# bristol_longshot.net
KiCad netlist of a schematic drawn in EAGLE
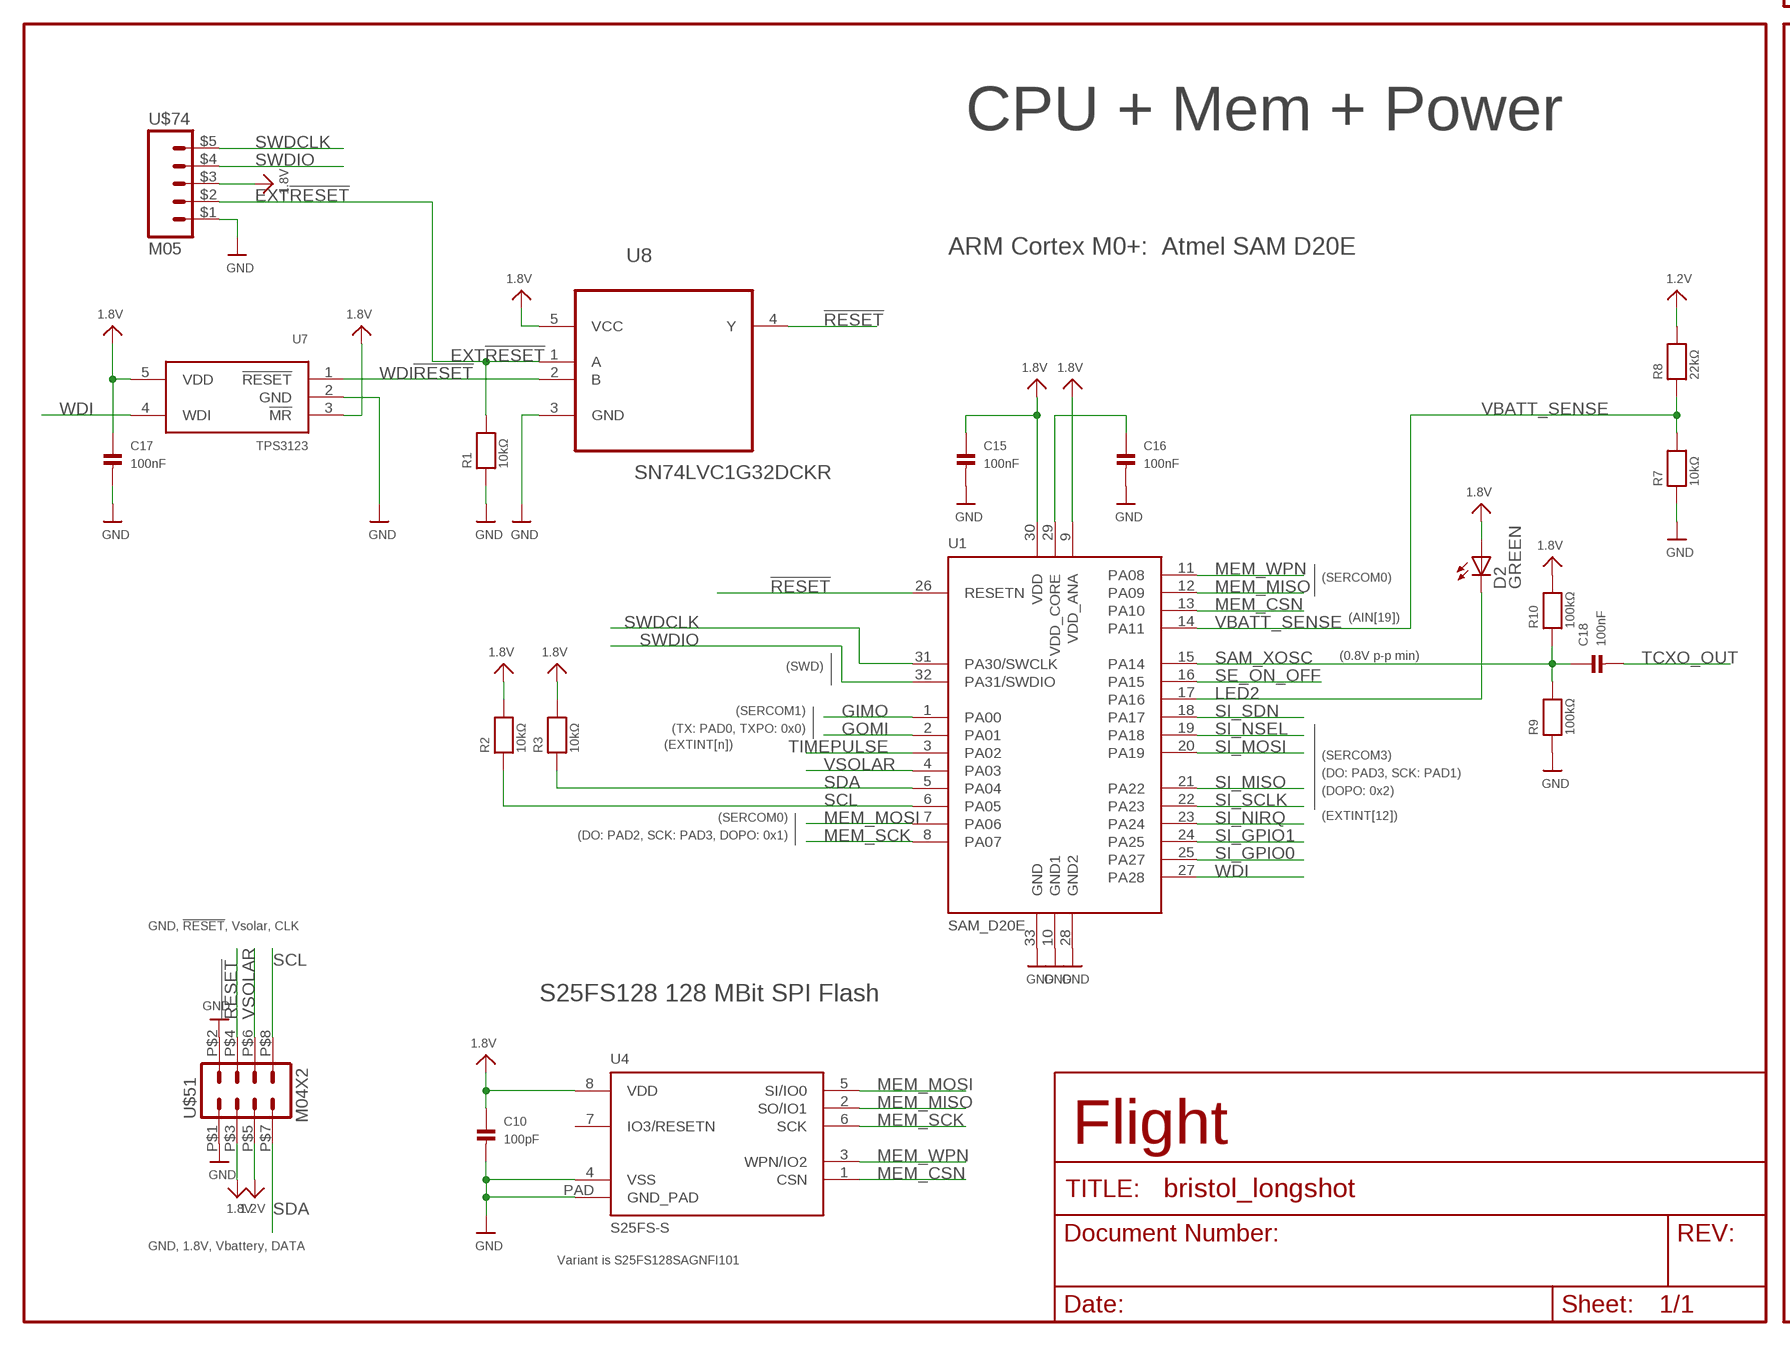
[diagram p0: schematic, sheet 1, part 1 of 2]
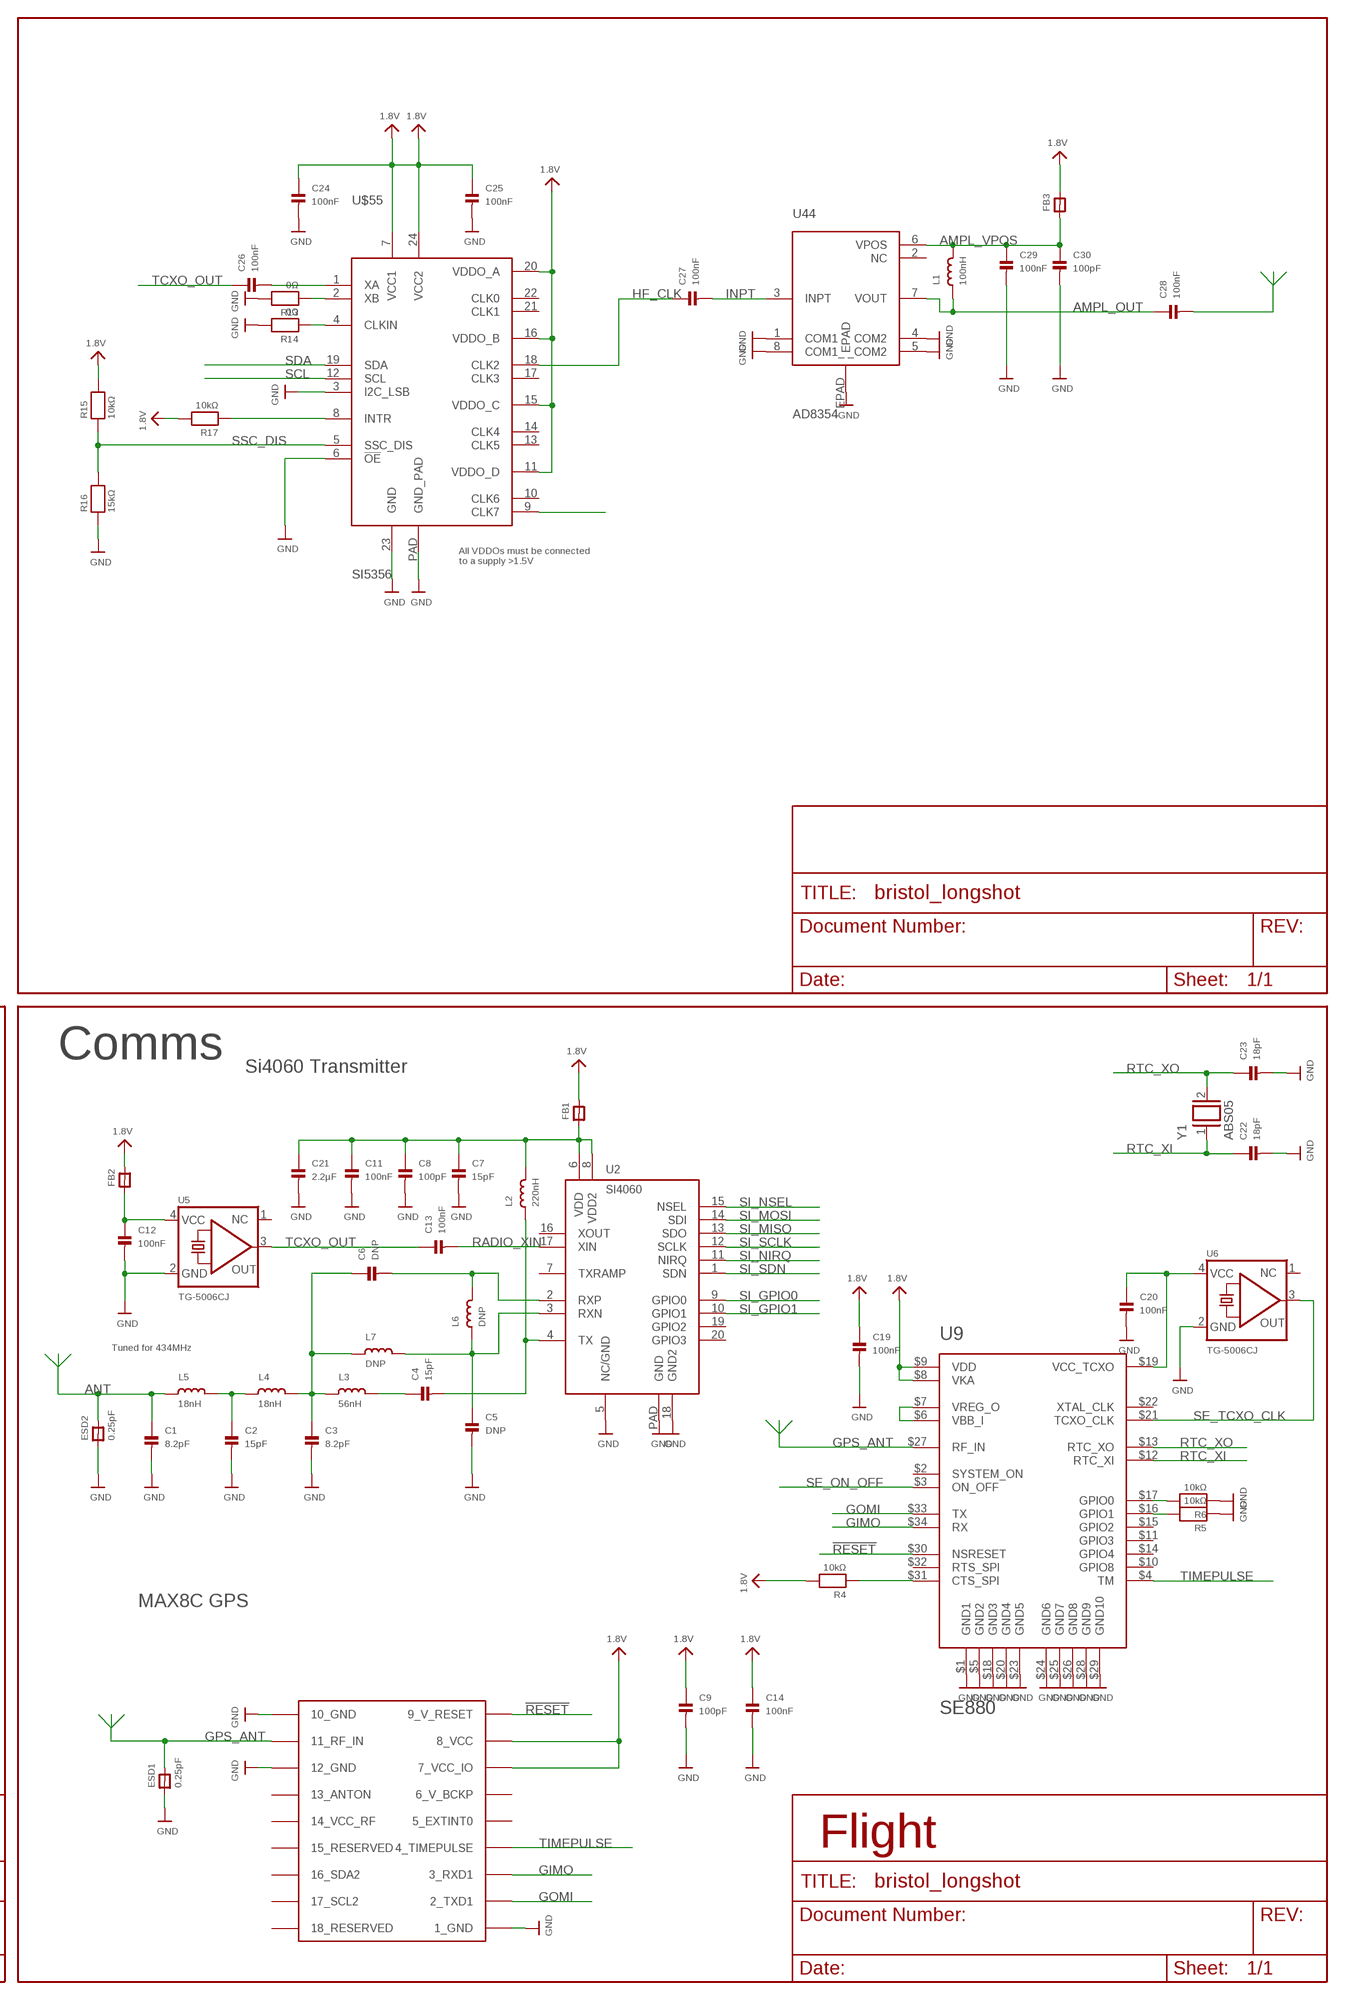
[diagram p1: schematic, sheet 1, part 2 of 2]

(export (version "E")
  (design (tool "Eeschema 10.0.6"))
  (components
    (comp (ref "C1")
      (value "8.2pF")
      (footprint "eagle-import:_0402")
      (libsource (lib "eagle-import") (part "CAP_CERAMIC_0402"))
    )
    (comp (ref "C2")
      (value "15pF")
      (footprint "eagle-import:_0402")
      (libsource (lib "eagle-import") (part "CAP_CERAMIC_0402"))
    )
    (comp (ref "C3")
      (value "8.2pF")
      (footprint "eagle-import:_0402")
      (libsource (lib "eagle-import") (part "CAP_CERAMIC_0402"))
    )
    (comp (ref "C4")
      (value "15pF")
      (footprint "eagle-import:_0402")
      (libsource (lib "eagle-import") (part "CAP_CERAMIC_0402"))
    )
    (comp (ref "C5")
      (value "DNP")
      (footprint "eagle-import:_0402")
      (libsource (lib "eagle-import") (part "CAP_CERAMIC_0402"))
    )
    (comp (ref "C6")
      (value "DNP")
      (footprint "eagle-import:_0402")
      (libsource (lib "eagle-import") (part "CAP_CERAMIC_0402"))
    )
    (comp (ref "C7")
      (value "15pF")
      (footprint "eagle-import:_0402")
      (libsource (lib "eagle-import") (part "CAP_CERAMIC_0402"))
    )
    (comp (ref "C8")
      (value "100pF")
      (footprint "eagle-import:_0402")
      (libsource (lib "eagle-import") (part "CAP_CERAMIC_0402"))
    )
    (comp (ref "C9")
      (value "100pF")
      (footprint "eagle-import:_0402")
      (libsource (lib "eagle-import") (part "CAP_CERAMIC_0402"))
    )
    (comp (ref "C10")
      (value "100pF")
      (footprint "eagle-import:_0402")
      (libsource (lib "eagle-import") (part "CAP_CERAMIC_0402"))
    )
    (comp (ref "C11")
      (value "100nF")
      (footprint "eagle-import:_0402")
      (libsource (lib "eagle-import") (part "CAP_CERAMIC_0402"))
    )
    (comp (ref "C12")
      (value "100nF")
      (footprint "eagle-import:_0402")
      (libsource (lib "eagle-import") (part "CAP_CERAMIC_0402"))
    )
    (comp (ref "C13")
      (value "100nF")
      (footprint "eagle-import:_0402")
      (libsource (lib "eagle-import") (part "CAP_CERAMIC_0402"))
    )
    (comp (ref "C14")
      (value "100nF")
      (footprint "eagle-import:_0402")
      (libsource (lib "eagle-import") (part "CAP_CERAMIC_0402"))
    )
    (comp (ref "C15")
      (value "100nF")
      (footprint "eagle-import:_0402")
      (libsource (lib "eagle-import") (part "CAP_CERAMIC_0402"))
    )
    (comp (ref "C16")
      (value "100nF")
      (footprint "eagle-import:_0402")
      (libsource (lib "eagle-import") (part "CAP_CERAMIC_0402"))
    )
    (comp (ref "C17")
      (value "100nF")
      (footprint "eagle-import:_0402")
      (libsource (lib "eagle-import") (part "CAP_CERAMIC_0402"))
    )
    (comp (ref "C18")
      (value "100nF")
      (footprint "eagle-import:_0402")
      (libsource (lib "eagle-import") (part "CAP_CERAMIC_0402"))
    )
    (comp (ref "C19")
      (value "100nF")
      (footprint "eagle-import:_0402")
      (libsource (lib "eagle-import") (part "CAP_CERAMIC_0402"))
    )
    (comp (ref "C20")
      (value "100nF")
      (footprint "eagle-import:_0402")
      (libsource (lib "eagle-import") (part "CAP_CERAMIC_0402"))
    )
    (comp (ref "C21")
      (value "2.2µF")
      (footprint "eagle-import:_0402")
      (libsource (lib "eagle-import") (part "CAP_CERAMIC_0402"))
    )
    (comp (ref "C22")
      (value "18pF")
      (footprint "eagle-import:_0402")
      (libsource (lib "eagle-import") (part "CAP_CERAMIC_0402"))
    )
    (comp (ref "C23")
      (value "18pF")
      (footprint "eagle-import:_0402")
      (libsource (lib "eagle-import") (part "CAP_CERAMIC_0402"))
    )
    (comp (ref "C24")
      (value "100nF")
      (footprint "eagle-import:_0402")
      (libsource (lib "eagle-import") (part "CAP_CERAMIC_0402"))
    )
    (comp (ref "C25")
      (value "100nF")
      (footprint "eagle-import:_0402")
      (libsource (lib "eagle-import") (part "CAP_CERAMIC_0402"))
    )
    (comp (ref "C26")
      (value "100nF")
      (footprint "eagle-import:_0402")
      (libsource (lib "eagle-import") (part "CAP_CERAMIC_0402"))
    )
    (comp (ref "C27")
      (value "100nF")
      (footprint "eagle-import:_0402")
      (libsource (lib "eagle-import") (part "CAP_CERAMIC_0402"))
    )
    (comp (ref "C28")
      (value "100nF")
      (footprint "eagle-import:_0402")
      (libsource (lib "eagle-import") (part "CAP_CERAMIC_0402"))
    )
    (comp (ref "C29")
      (value "100nF")
      (footprint "eagle-import:_0402")
      (libsource (lib "eagle-import") (part "CAP_CERAMIC_0402"))
    )
    (comp (ref "C30")
      (value "100pF")
      (footprint "eagle-import:_0402")
      (libsource (lib "eagle-import") (part "CAP_CERAMIC_0402"))
    )
    (comp (ref "D2")
      (value "GREEN")
      (footprint "eagle-import:CHIPLED_0603")
      (libsource (lib "eagle-import") (part "LEDCHIPLED_0603"))
    )
    (comp (ref "ESD1")
      (value "0.25pF")
      (footprint "eagle-import:_0603MP")
      (libsource (lib "eagle-import") (part "FERRITE_0603MP"))
    )
    (comp (ref "ESD2")
      (value "0.25pF")
      (footprint "eagle-import:_0603MP")
      (libsource (lib "eagle-import") (part "FERRITE_0603MP"))
    )
    (comp (ref "FB1")
      (value "FERRITE_0402")
      (footprint "eagle-import:_0402")
      (libsource (lib "eagle-import") (part "FERRITE_0402"))
    )
    (comp (ref "FB2")
      (value "FERRITE_0402")
      (footprint "eagle-import:_0402")
      (libsource (lib "eagle-import") (part "FERRITE_0402"))
    )
    (comp (ref "FB3")
      (value "FERRITE_0402")
      (footprint "eagle-import:_0402")
      (libsource (lib "eagle-import") (part "FERRITE_0402"))
    )
    (comp (ref "L1")
      (value "100nH")
      (footprint "eagle-import:_0402")
      (libsource (lib "eagle-import") (part "INDUCTOR_0402"))
    )
    (comp (ref "L2")
      (value "220nH")
      (footprint "eagle-import:_0402")
      (libsource (lib "eagle-import") (part "INDUCTOR_0402"))
    )
    (comp (ref "L3")
      (value "56nH")
      (footprint "eagle-import:_0402")
      (libsource (lib "eagle-import") (part "INDUCTOR_0402"))
    )
    (comp (ref "L4")
      (value "18nH")
      (footprint "eagle-import:_0402")
      (libsource (lib "eagle-import") (part "INDUCTOR_0402"))
    )
    (comp (ref "L5")
      (value "18nH")
      (footprint "eagle-import:_0402")
      (libsource (lib "eagle-import") (part "INDUCTOR_0402"))
    )
    (comp (ref "L6")
      (value "DNP")
      (footprint "eagle-import:_0402")
      (libsource (lib "eagle-import") (part "INDUCTOR_0402"))
    )
    (comp (ref "L7")
      (value "DNP")
      (footprint "eagle-import:_0402")
      (libsource (lib "eagle-import") (part "INDUCTOR_0402"))
    )
    (comp (ref "R1")
      (value "10kΩ")
      (footprint "eagle-import:_0402")
      (libsource (lib "eagle-import") (part "RESISTOR_0402"))
    )
    (comp (ref "R2")
      (value "10kΩ")
      (footprint "eagle-import:_0402")
      (libsource (lib "eagle-import") (part "RESISTOR_0402"))
    )
    (comp (ref "R3")
      (value "10kΩ")
      (footprint "eagle-import:_0402")
      (libsource (lib "eagle-import") (part "RESISTOR_0402"))
    )
    (comp (ref "R4")
      (value "10kΩ")
      (footprint "eagle-import:_0402")
      (libsource (lib "eagle-import") (part "RESISTOR_0402"))
    )
    (comp (ref "R5")
      (value "10kΩ")
      (footprint "eagle-import:_0402")
      (libsource (lib "eagle-import") (part "RESISTOR_0402"))
    )
    (comp (ref "R6")
      (value "10kΩ")
      (footprint "eagle-import:_0402")
      (libsource (lib "eagle-import") (part "RESISTOR_0402"))
    )
    (comp (ref "R7")
      (value "10kΩ")
      (footprint "eagle-import:_0402")
      (libsource (lib "eagle-import") (part "RESISTOR_0402"))
    )
    (comp (ref "R8")
      (value "22kΩ")
      (footprint "eagle-import:_0402")
      (libsource (lib "eagle-import") (part "RESISTOR_0402"))
    )
    (comp (ref "R9")
      (value "100kΩ")
      (footprint "eagle-import:_0402")
      (libsource (lib "eagle-import") (part "RESISTOR_0402"))
    )
    (comp (ref "R10")
      (value "100kΩ")
      (footprint "eagle-import:_0402")
      (libsource (lib "eagle-import") (part "RESISTOR_0402"))
    )
    (comp (ref "R13")
      (value "0Ω")
      (footprint "eagle-import:_0402")
      (libsource (lib "eagle-import") (part "RESISTOR_0402"))
    )
    (comp (ref "R14")
      (value "0Ω")
      (footprint "eagle-import:_0402")
      (libsource (lib "eagle-import") (part "RESISTOR_0402"))
    )
    (comp (ref "R15")
      (value "10kΩ")
      (footprint "eagle-import:_0402")
      (libsource (lib "eagle-import") (part "RESISTOR_0402"))
    )
    (comp (ref "R16")
      (value "15kΩ")
      (footprint "eagle-import:_0402")
      (libsource (lib "eagle-import") (part "RESISTOR_0402"))
    )
    (comp (ref "R17")
      (value "10kΩ")
      (footprint "eagle-import:_0402")
      (libsource (lib "eagle-import") (part "RESISTOR_0402"))
    )
    (comp (ref "U$51")
      (value "M04X2")
      (footprint "eagle-import:M04X2")
      (libsource (lib "eagle-import") (part "M04X2"))
    )
    (comp (ref "U$55")
      (value "SI5356")
      (footprint "eagle-import:QFN24_4MM")
      (libsource (lib "eagle-import") (part "SI5356"))
    )
    (comp (ref "U$74")
      (value "M05")
      (footprint "eagle-import:M05_SIDE")
      (libsource (lib "eagle-import") (part "M05"))
    )
    (comp (ref "U1")
      (value "SAM_D20E")
      (footprint "eagle-import:QFN32_5MM")
      (libsource (lib "eagle-import") (part "SAM_D20E"))
    )
    (comp (ref "U2")
      (value "SI4060")
      (footprint "eagle-import:QFN20")
      (libsource (lib "eagle-import") (part "SI4060"))
    )
    (comp (ref "U3")
      (value "UBLOX_MAX")
      (footprint "eagle-import:UBLOX_MAX")
      (libsource (lib "eagle-import") (part "UBLOX_MAX"))
    )
    (comp (ref "U4")
      (value "S25FS-S")
      (footprint "eagle-import:WSON8")
      (libsource (lib "eagle-import") (part "S25FS-S"))
    )
    (comp (ref "U5")
      (value "TG-5006CJ")
      (footprint "eagle-import:TC-5006CJ")
      (libsource (lib "eagle-import") (part "TG-5006CJ"))
    )
    (comp (ref "U6")
      (value "TG-5006CJ")
      (footprint "eagle-import:TC-5006CJ")
      (libsource (lib "eagle-import") (part "TG-5006CJ"))
    )
    (comp (ref "U7")
      (value "TPS3123")
      (footprint "eagle-import:SOT23-5")
      (libsource (lib "eagle-import") (part "TPS3123"))
    )
    (comp (ref "U8")
      (value "SN74LVC1G32DCKR")
      (footprint "eagle-import:SOT65P210X110-5N")
      (libsource (lib "eagle-import") (part "SN74LVC1G32DCKR"))
    )
    (comp (ref "U9")
      (value "SE880")
      (footprint "eagle-import:SE880")
      (libsource (lib "eagle-import") (part "SE880"))
    )
    (comp (ref "U44")
      (value "AD8354")
      (footprint "eagle-import:LFCSP_VD_8")
      (libsource (lib "eagle-import") (part "AD8354"))
    )
    (comp (ref "Y1")
      (value "ABS05")
      (footprint "eagle-import:ABS05")
      (libsource (lib "eagle-import") (part "ABS05"))
    )
  )
  (nets
    (net (code "1") (name "/AMPL_OUT") (class "Default")
      (node (ref "C28") (pin "1") (pinfunction "P$1_1") (pintype "passive"))
      (node (ref "L1") (pin "1") (pinfunction "1_1") (pintype "passive"))
      (node (ref "U44") (pin "7") (pinfunction "VOUT_7") (pintype "bidirectional"))
    )
    (net (code "2") (name "/AMPL_VPOS") (class "Default")
      (node (ref "C29") (pin "1") (pinfunction "P$1_1") (pintype "passive"))
      (node (ref "C30") (pin "1") (pinfunction "P$1_1") (pintype "passive"))
      (node (ref "FB3") (pin "1") (pinfunction "P$1_1") (pintype "passive"))
      (node (ref "L1") (pin "2") (pinfunction "2_2") (pintype "passive"))
      (node (ref "U44") (pin "6") (pinfunction "VPOS_6") (pintype "bidirectional"))
    )
    (net (code "3") (name "/ANT") (class "Default")
      (node (ref "C1") (pin "1") (pinfunction "P$1_1") (pintype "passive"))
      (node (ref "ESD2") (pin "2") (pinfunction "P$2_2") (pintype "passive"))
      (node (ref "L5") (pin "1") (pinfunction "1_1") (pintype "passive"))
    )
    (net (code "4") (name "/EXT~{RESET}") (class "Default")
      (node (ref "R1") (pin "2") (pinfunction "2_2") (pintype "passive"))
      (node (ref "U$74") (pin "$2") (pinfunction "2_$2") (pintype "passive"))
      (node (ref "U8") (pin "1") (pinfunction "A_1") (pintype "input"))
    )
    (net (code "5") (name "/GIMO") (class "Default")
      (node (ref "U1") (pin "1") (pinfunction "PA00_1") (pintype "bidirectional"))
      (node (ref "U3") (pin "3_RXD1") (pinfunction "3_RXD1_3_RXD1") (pintype "bidirectional"))
      (node (ref "U9") (pin "$34") (pinfunction "RX_$34") (pintype "bidirectional"))
    )
    (net (code "6") (name "/GOMI") (class "Default")
      (node (ref "U1") (pin "2") (pinfunction "PA01_2") (pintype "bidirectional"))
      (node (ref "U3") (pin "2_TXD1") (pinfunction "2_TXD1_2_TXD1") (pintype "bidirectional"))
      (node (ref "U9") (pin "$33") (pinfunction "TX_$33") (pintype "bidirectional"))
    )
    (net (code "7") (name "/GPS_ANT") (class "Default")
      (node (ref "ESD1") (pin "2") (pinfunction "P$2_2") (pintype "passive"))
      (node (ref "U3") (pin "11_RF_IN") (pinfunction "11_RF_IN_11_RF_IN") (pintype "bidirectional"))
      (node (ref "U9") (pin "$27") (pinfunction "RF_IN_$27") (pintype "bidirectional"))
    )
    (net (code "8") (name "/HF_CLK") (class "Default")
      (node (ref "C27") (pin "1") (pinfunction "P$1_1") (pintype "passive"))
      (node (ref "U$55") (pin "18") (pinfunction "CLK2_18") (pintype "bidirectional"))
    )
    (net (code "9") (name "/INPT") (class "Default")
      (node (ref "C27") (pin "2") (pinfunction "P$2_2") (pintype "passive"))
      (node (ref "U44") (pin "3") (pinfunction "INPT_3") (pintype "bidirectional"))
    )
    (net (code "10") (name "/LED2") (class "Default")
      (node (ref "D2") (pin "C") (pinfunction "C_C") (pintype "passive"))
      (node (ref "U1") (pin "17") (pinfunction "PA16_17") (pintype "bidirectional"))
    )
    (net (code "11") (name "/MEM_CSN") (class "Default")
      (node (ref "U1") (pin "13") (pinfunction "PA10_13") (pintype "bidirectional"))
      (node (ref "U4") (pin "1") (pinfunction "CSN_1") (pintype "input"))
    )
    (net (code "12") (name "/MEM_MISO") (class "Default")
      (node (ref "U1") (pin "12") (pinfunction "PA09_12") (pintype "bidirectional"))
      (node (ref "U4") (pin "2") (pinfunction "SO/IO1_2") (pintype "output"))
    )
    (net (code "13") (name "/MEM_MOSI") (class "Default")
      (node (ref "U1") (pin "7") (pinfunction "PA06_7") (pintype "bidirectional"))
      (node (ref "U4") (pin "5") (pinfunction "SI/IO0_5") (pintype "bidirectional"))
    )
    (net (code "14") (name "/MEM_SCK") (class "Default")
      (node (ref "U1") (pin "8") (pinfunction "PA07_8") (pintype "bidirectional"))
      (node (ref "U4") (pin "6") (pinfunction "SCK_6") (pintype "input"))
    )
    (net (code "15") (name "/MEM_WPN") (class "Default")
      (node (ref "U1") (pin "11") (pinfunction "PA08_11") (pintype "bidirectional"))
      (node (ref "U4") (pin "3") (pinfunction "WPN/IO2_3") (pintype "output"))
    )
    (net (code "16") (name "/RADIO_XIN") (class "Default")
      (node (ref "C13") (pin "2") (pinfunction "P$2_2") (pintype "passive"))
      (node (ref "U2") (pin "17") (pinfunction "XIN_17") (pintype "input"))
    )
    (net (code "17") (name "/RTC_XI") (class "Default")
      (node (ref "C22") (pin "1") (pinfunction "P$1_1") (pintype "passive"))
      (node (ref "U9") (pin "$12") (pinfunction "RTC_XI_$12") (pintype "bidirectional"))
      (node (ref "Y1") (pin "1") (pinfunction "1_1") (pintype "passive"))
    )
    (net (code "18") (name "/RTC_XO") (class "Default")
      (node (ref "C23") (pin "1") (pinfunction "P$1_1") (pintype "passive"))
      (node (ref "U9") (pin "$13") (pinfunction "RTC_XO_$13") (pintype "bidirectional"))
      (node (ref "Y1") (pin "2") (pinfunction "2_2") (pintype "passive"))
    )
    (net (code "19") (name "/SAM_XOSC") (class "Default")
      (node (ref "C18") (pin "1") (pinfunction "P$1_1") (pintype "passive"))
      (node (ref "R10") (pin "1") (pinfunction "1_1") (pintype "passive"))
      (node (ref "R9") (pin "2") (pinfunction "2_2") (pintype "passive"))
      (node (ref "U1") (pin "15") (pinfunction "PA14_15") (pintype "bidirectional"))
    )
    (net (code "20") (name "/SCL") (class "Default")
      (node (ref "R2") (pin "1") (pinfunction "1_1") (pintype "passive"))
      (node (ref "U$51") (pin "P$8") (pinfunction "8_P$8") (pintype "passive"))
      (node (ref "U$55") (pin "12") (pinfunction "SCL_12") (pintype "bidirectional"))
      (node (ref "U1") (pin "6") (pinfunction "PA05_6") (pintype "bidirectional"))
    )
    (net (code "21") (name "/SDA") (class "Default")
      (node (ref "R3") (pin "1") (pinfunction "1_1") (pintype "passive"))
      (node (ref "U$51") (pin "P$7") (pinfunction "7_P$7") (pintype "passive"))
      (node (ref "U$55") (pin "19") (pinfunction "SDA_19") (pintype "bidirectional"))
      (node (ref "U1") (pin "5") (pinfunction "PA04_5") (pintype "bidirectional"))
    )
    (net (code "22") (name "/SE_ON_OFF") (class "Default")
      (node (ref "U1") (pin "16") (pinfunction "PA15_16") (pintype "bidirectional"))
      (node (ref "U9") (pin "$3") (pinfunction "ON_OFF_$3") (pintype "bidirectional"))
    )
    (net (code "23") (name "/SE_TCXO_CLK") (class "Default")
      (node (ref "U6") (pin "3") (pinfunction "OUT_3") (pintype "output"))
      (node (ref "U9") (pin "$21") (pinfunction "TCXO_CLK_$21") (pintype "bidirectional"))
    )
    (net (code "24") (name "/SI_GPIO0") (class "Default")
      (node (ref "U1") (pin "25") (pinfunction "PA27_25") (pintype "bidirectional"))
      (node (ref "U2") (pin "9") (pinfunction "GPIO0_9") (pintype "bidirectional"))
    )
    (net (code "25") (name "/SI_GPIO1") (class "Default")
      (node (ref "U1") (pin "24") (pinfunction "PA25_24") (pintype "bidirectional"))
      (node (ref "U2") (pin "10") (pinfunction "GPIO1_10") (pintype "bidirectional"))
    )
    (net (code "26") (name "/SI_MISO") (class "Default")
      (node (ref "U1") (pin "21") (pinfunction "PA22_21") (pintype "bidirectional"))
      (node (ref "U2") (pin "13") (pinfunction "SDO_13") (pintype "output"))
    )
    (net (code "27") (name "/SI_MOSI") (class "Default")
      (node (ref "U1") (pin "20") (pinfunction "PA19_20") (pintype "bidirectional"))
      (node (ref "U2") (pin "14") (pinfunction "SDI_14") (pintype "bidirectional"))
    )
    (net (code "28") (name "/SI_NIRQ") (class "Default")
      (node (ref "U1") (pin "23") (pinfunction "PA24_23") (pintype "bidirectional"))
      (node (ref "U2") (pin "11") (pinfunction "NIRQ_11") (pintype "output"))
    )
    (net (code "29") (name "/SI_NSEL") (class "Default")
      (node (ref "U1") (pin "19") (pinfunction "PA18_19") (pintype "bidirectional"))
      (node (ref "U2") (pin "15") (pinfunction "NSEL_15") (pintype "input"))
    )
    (net (code "30") (name "/SI_SCLK") (class "Default")
      (node (ref "U1") (pin "22") (pinfunction "PA23_22") (pintype "bidirectional"))
      (node (ref "U2") (pin "12") (pinfunction "SCLK_12") (pintype "input"))
    )
    (net (code "31") (name "/SI_SDN") (class "Default")
      (node (ref "U1") (pin "18") (pinfunction "PA17_18") (pintype "bidirectional"))
      (node (ref "U2") (pin "1") (pinfunction "SDN_1") (pintype "input"))
    )
    (net (code "32") (name "/SSC_DIS") (class "Default")
      (node (ref "R15") (pin "1") (pinfunction "1_1") (pintype "passive"))
      (node (ref "R16") (pin "2") (pinfunction "2_2") (pintype "passive"))
      (node (ref "U$55") (pin "5") (pinfunction "SSC_DIS_5") (pintype "bidirectional"))
    )
    (net (code "33") (name "/SWDCLK") (class "Default")
      (node (ref "U$74") (pin "$5") (pinfunction "5_$5") (pintype "passive"))
      (node (ref "U1") (pin "31") (pinfunction "PA30/SWCLK_31") (pintype "bidirectional"))
    )
    (net (code "34") (name "/SWDIO") (class "Default")
      (node (ref "U$74") (pin "$4") (pinfunction "4_$4") (pintype "passive"))
      (node (ref "U1") (pin "32") (pinfunction "PA31/SWDIO_32") (pintype "bidirectional"))
    )
    (net (code "35") (name "/TCXO_OUT") (class "Default")
      (node (ref "C13") (pin "1") (pinfunction "P$1_1") (pintype "passive"))
      (node (ref "C18") (pin "2") (pinfunction "P$2_2") (pintype "passive"))
      (node (ref "C26") (pin "1") (pinfunction "P$1_1") (pintype "passive"))
      (node (ref "U5") (pin "3") (pinfunction "OUT_3") (pintype "output"))
    )
    (net (code "36") (name "/TIMEPULSE") (class "Default")
      (node (ref "U1") (pin "3") (pinfunction "PA02_3") (pintype "bidirectional"))
      (node (ref "U3") (pin "4_TIMEPULSE") (pinfunction "4_TIMEPULSE_4_TIMEPULSE") (pintype "bidirectional"))
      (node (ref "U9") (pin "$4") (pinfunction "TM_$4") (pintype "bidirectional"))
    )
    (net (code "37") (name "/VBATT_SENSE") (class "Default")
      (node (ref "R7") (pin "2") (pinfunction "2_2") (pintype "passive"))
      (node (ref "R8") (pin "1") (pinfunction "1_1") (pintype "passive"))
      (node (ref "U1") (pin "14") (pinfunction "PA11_14") (pintype "bidirectional"))
    )
    (net (code "38") (name "/VSOLAR") (class "Default")
      (node (ref "U$51") (pin "P$6") (pinfunction "6_P$6") (pintype "passive"))
      (node (ref "U1") (pin "4") (pinfunction "PA03_4") (pintype "bidirectional"))
    )
    (net (code "39") (name "/WDI") (class "Default")
      (node (ref "U1") (pin "27") (pinfunction "PA28_27") (pintype "bidirectional"))
      (node (ref "U7") (pin "4") (pinfunction "WDI_4") (pintype "bidirectional"))
    )
    (net (code "40") (name "/WDI~{RESET}") (class "Default")
      (node (ref "U7") (pin "1") (pinfunction "~{RESET}_1") (pintype "bidirectional"))
      (node (ref "U8") (pin "2") (pinfunction "B_2") (pintype "input"))
    )
    (net (code "41") (name "/~{RESET}") (class "Default")
      (node (ref "U$51") (pin "P$4") (pinfunction "4_P$4") (pintype "passive"))
      (node (ref "U1") (pin "26") (pinfunction "RESETN_26") (pintype "input"))
      (node (ref "U3") (pin "9_V_RESET") (pinfunction "9_V_RESET_9_V_RESET") (pintype "power_in"))
      (node (ref "U8") (pin "4") (pinfunction "Y_4") (pintype "output"))
      (node (ref "U9") (pin "$30") (pinfunction "NSRESET_$30") (pintype "bidirectional"))
    )
    (net (code "42") (name "1.2V") (class "Default")
      (node (ref "R8") (pin "2") (pinfunction "2_2") (pintype "passive"))
      (node (ref "U$51") (pin "P$5") (pinfunction "5_P$5") (pintype "passive"))
    )
    (net (code "43") (name "1.8V") (class "Default")
      (node (ref "C10") (pin "1") (pinfunction "P$1_1") (pintype "passive"))
      (node (ref "C14") (pin "1") (pinfunction "P$1_1") (pintype "passive"))
      (node (ref "C15") (pin "1") (pinfunction "P$1_1") (pintype "passive"))
      (node (ref "C17") (pin "1") (pinfunction "P$1_1") (pintype "passive"))
      (node (ref "C19") (pin "1") (pinfunction "P$1_1") (pintype "passive"))
      (node (ref "C24") (pin "1") (pinfunction "P$1_1") (pintype "passive"))
      (node (ref "C25") (pin "1") (pinfunction "P$1_1") (pintype "passive"))
      (node (ref "C9") (pin "1") (pinfunction "P$1_1") (pintype "passive"))
      (node (ref "D2") (pin "A") (pinfunction "A_A") (pintype "passive"))
      (node (ref "FB1") (pin "2") (pinfunction "P$2_2") (pintype "passive"))
      (node (ref "FB2") (pin "2") (pinfunction "P$2_2") (pintype "passive"))
      (node (ref "FB3") (pin "2") (pinfunction "P$2_2") (pintype "passive"))
      (node (ref "R10") (pin "2") (pinfunction "2_2") (pintype "passive"))
      (node (ref "R15") (pin "2") (pinfunction "2_2") (pintype "passive"))
      (node (ref "R17") (pin "2") (pinfunction "2_2") (pintype "passive"))
      (node (ref "R2") (pin "2") (pinfunction "2_2") (pintype "passive"))
      (node (ref "R3") (pin "2") (pinfunction "2_2") (pintype "passive"))
      (node (ref "R4") (pin "2") (pinfunction "2_2") (pintype "passive"))
      (node (ref "U$51") (pin "P$3") (pinfunction "3_P$3") (pintype "passive"))
      (node (ref "U$55") (pin "11") (pinfunction "VDDO_D_11") (pintype "bidirectional"))
      (node (ref "U$55") (pin "15") (pinfunction "VDDO_C_15") (pintype "bidirectional"))
      (node (ref "U$55") (pin "16") (pinfunction "VDDO_B_16") (pintype "bidirectional"))
      (node (ref "U$55") (pin "20") (pinfunction "VDDO_A_20") (pintype "bidirectional"))
      (node (ref "U$55") (pin "24") (pinfunction "VCC2_24") (pintype "bidirectional"))
      (node (ref "U$55") (pin "7") (pinfunction "VCC1_7") (pintype "bidirectional"))
      (node (ref "U$74") (pin "$3") (pinfunction "3_$3") (pintype "passive"))
      (node (ref "U1") (pin "30") (pinfunction "VDD_30") (pintype "power_in"))
      (node (ref "U1") (pin "9") (pinfunction "VDD_ANA_9") (pintype "power_in"))
      (node (ref "U3") (pin "7_VCC_IO") (pinfunction "7_VCC_IO_7_VCC_IO") (pintype "power_in"))
      (node (ref "U3") (pin "8_VCC") (pinfunction "8_VCC_8_VCC") (pintype "power_in"))
      (node (ref "U4") (pin "8") (pinfunction "VDD_8") (pintype "power_in"))
      (node (ref "U7") (pin "3") (pinfunction "~{MR}_3") (pintype "bidirectional"))
      (node (ref "U7") (pin "5") (pinfunction "VDD_5") (pintype "bidirectional"))
      (node (ref "U8") (pin "5") (pinfunction "VCC_5") (pintype "power_in"))
      (node (ref "U9") (pin "$8") (pinfunction "VKA_$8") (pintype "bidirectional"))
      (node (ref "U9") (pin "$9") (pinfunction "VDD_$9") (pintype "bidirectional"))
    )
    (net (code "44") (name "GND") (class "Default")
      (node (ref "C1") (pin "2") (pinfunction "P$2_2") (pintype "passive"))
      (node (ref "C10") (pin "2") (pinfunction "P$2_2") (pintype "passive"))
      (node (ref "C11") (pin "2") (pinfunction "P$2_2") (pintype "passive"))
      (node (ref "C12") (pin "2") (pinfunction "P$2_2") (pintype "passive"))
      (node (ref "C14") (pin "2") (pinfunction "P$2_2") (pintype "passive"))
      (node (ref "C15") (pin "2") (pinfunction "P$2_2") (pintype "passive"))
      (node (ref "C16") (pin "2") (pinfunction "P$2_2") (pintype "passive"))
      (node (ref "C17") (pin "2") (pinfunction "P$2_2") (pintype "passive"))
      (node (ref "C19") (pin "2") (pinfunction "P$2_2") (pintype "passive"))
      (node (ref "C2") (pin "2") (pinfunction "P$2_2") (pintype "passive"))
      (node (ref "C20") (pin "2") (pinfunction "P$2_2") (pintype "passive"))
      (node (ref "C21") (pin "2") (pinfunction "P$2_2") (pintype "passive"))
      (node (ref "C22") (pin "2") (pinfunction "P$2_2") (pintype "passive"))
      (node (ref "C23") (pin "2") (pinfunction "P$2_2") (pintype "passive"))
      (node (ref "C24") (pin "2") (pinfunction "P$2_2") (pintype "passive"))
      (node (ref "C25") (pin "2") (pinfunction "P$2_2") (pintype "passive"))
      (node (ref "C29") (pin "2") (pinfunction "P$2_2") (pintype "passive"))
      (node (ref "C3") (pin "2") (pinfunction "P$2_2") (pintype "passive"))
      (node (ref "C30") (pin "2") (pinfunction "P$2_2") (pintype "passive"))
      (node (ref "C5") (pin "2") (pinfunction "P$2_2") (pintype "passive"))
      (node (ref "C7") (pin "2") (pinfunction "P$2_2") (pintype "passive"))
      (node (ref "C8") (pin "2") (pinfunction "P$2_2") (pintype "passive"))
      (node (ref "C9") (pin "2") (pinfunction "P$2_2") (pintype "passive"))
      (node (ref "ESD1") (pin "1") (pinfunction "P$1_1") (pintype "passive"))
      (node (ref "ESD2") (pin "1") (pinfunction "P$1_1") (pintype "passive"))
      (node (ref "R1") (pin "1") (pinfunction "1_1") (pintype "passive"))
      (node (ref "R13") (pin "2") (pinfunction "2_2") (pintype "passive"))
      (node (ref "R14") (pin "2") (pinfunction "2_2") (pintype "passive"))
      (node (ref "R16") (pin "1") (pinfunction "1_1") (pintype "passive"))
      (node (ref "R5") (pin "1") (pinfunction "1_1") (pintype "passive"))
      (node (ref "R6") (pin "1") (pinfunction "1_1") (pintype "passive"))
      (node (ref "R7") (pin "1") (pinfunction "1_1") (pintype "passive"))
      (node (ref "R9") (pin "1") (pinfunction "1_1") (pintype "passive"))
      (node (ref "U$51") (pin "P$1") (pinfunction "1_P$1") (pintype "passive"))
      (node (ref "U$51") (pin "P$2") (pinfunction "2_P$2") (pintype "passive"))
      (node (ref "U$55") (pin "23") (pinfunction "GND_23") (pintype "bidirectional"))
      (node (ref "U$55") (pin "3") (pinfunction "I2C_LSB_3") (pintype "bidirectional"))
      (node (ref "U$55") (pin "6") (pinfunction "~{OE}_6") (pintype "bidirectional"))
      (node (ref "U$55") (pin "PAD") (pinfunction "GND_PAD_PAD") (pintype "bidirectional"))
      (node (ref "U$74") (pin "$1") (pinfunction "1_$1") (pintype "passive"))
      (node (ref "U1") (pin "10") (pinfunction "GND1_10") (pintype "power_in"))
      (node (ref "U1") (pin "28") (pinfunction "GND2_28") (pintype "power_in"))
      (node (ref "U1") (pin "33") (pinfunction "GND_33") (pintype "power_in"))
      (node (ref "U2") (pin "18") (pinfunction "GND2_18") (pintype "power_in"))
      (node (ref "U2") (pin "5") (pinfunction "NC/GND_5") (pintype "bidirectional"))
      (node (ref "U2") (pin "PAD") (pinfunction "GND_PAD") (pintype "power_in"))
      (node (ref "U3") (pin "10_GND") (pinfunction "10_GND_10_GND") (pintype "power_in"))
      (node (ref "U3") (pin "12_GND") (pinfunction "12_GND_12_GND") (pintype "power_in"))
      (node (ref "U3") (pin "1_GND") (pinfunction "1_GND_1_GND") (pintype "power_in"))
      (node (ref "U4") (pin "4") (pinfunction "VSS_4") (pintype "power_in"))
      (node (ref "U4") (pin "PAD") (pinfunction "GND_PAD_PAD") (pintype "power_in"))
      (node (ref "U44") (pin "1") (pinfunction "COM1_1") (pintype "bidirectional"))
      (node (ref "U44") (pin "4") (pinfunction "COM2_4") (pintype "bidirectional"))
      (node (ref "U44") (pin "5") (pinfunction "_COM2_5") (pintype "bidirectional"))
      (node (ref "U44") (pin "8") (pinfunction "COM1__8") (pintype "bidirectional"))
      (node (ref "U44") (pin "EPAD") (pinfunction "EPAD_EPAD") (pintype "bidirectional"))
      (node (ref "U5") (pin "2") (pinfunction "GND_2") (pintype "power_in"))
      (node (ref "U6") (pin "2") (pinfunction "GND_2") (pintype "power_in"))
      (node (ref "U7") (pin "2") (pinfunction "GND_2") (pintype "bidirectional"))
      (node (ref "U8") (pin "3") (pinfunction "GND_3") (pintype "passive"))
      (node (ref "U9") (pin "$1") (pinfunction "GND1_$1") (pintype "bidirectional"))
      (node (ref "U9") (pin "$18") (pinfunction "GND3_$18") (pintype "bidirectional"))
      (node (ref "U9") (pin "$20") (pinfunction "GND4_$20") (pintype "bidirectional"))
      (node (ref "U9") (pin "$23") (pinfunction "GND5_$23") (pintype "bidirectional"))
      (node (ref "U9") (pin "$24") (pinfunction "GND6_$24") (pintype "bidirectional"))
      (node (ref "U9") (pin "$25") (pinfunction "GND7_$25") (pintype "bidirectional"))
      (node (ref "U9") (pin "$26") (pinfunction "GND8_$26") (pintype "bidirectional"))
      (node (ref "U9") (pin "$28") (pinfunction "GND9_$28") (pintype "bidirectional"))
      (node (ref "U9") (pin "$29") (pinfunction "GND10_$29") (pintype "bidirectional"))
      (node (ref "U9") (pin "$5") (pinfunction "GND2_$5") (pintype "bidirectional"))
    )
    (net (code "45") (name "Net-(C2-P$1)") (class "Default")
      (node (ref "C2") (pin "1") (pinfunction "P$1_1") (pintype "passive"))
      (node (ref "L4") (pin "1") (pinfunction "1_1") (pintype "passive"))
      (node (ref "L5") (pin "2") (pinfunction "2_2") (pintype "passive"))
    )
    (net (code "46") (name "Net-(C3-P$1)") (class "Default")
      (node (ref "C3") (pin "1") (pinfunction "P$1_1") (pintype "passive"))
      (node (ref "C6") (pin "1") (pinfunction "P$1_1") (pintype "passive"))
      (node (ref "L3") (pin "1") (pinfunction "1_1") (pintype "passive"))
      (node (ref "L4") (pin "2") (pinfunction "2_2") (pintype "passive"))
      (node (ref "L7") (pin "1") (pinfunction "1_1") (pintype "passive"))
    )
    (net (code "47") (name "Net-(C4-P$1)") (class "Default")
      (node (ref "C4") (pin "1") (pinfunction "P$1_1") (pintype "passive"))
      (node (ref "L3") (pin "2") (pinfunction "2_2") (pintype "passive"))
    )
    (net (code "48") (name "Net-(C4-P$2)") (class "Default")
      (node (ref "C4") (pin "2") (pinfunction "P$2_2") (pintype "passive"))
      (node (ref "L2") (pin "1") (pinfunction "1_1") (pintype "passive"))
      (node (ref "U2") (pin "4") (pinfunction "TX_4") (pintype "output"))
    )
    (net (code "49") (name "Net-(C5-P$1)") (class "Default")
      (node (ref "C5") (pin "1") (pinfunction "P$1_1") (pintype "passive"))
      (node (ref "L6") (pin "1") (pinfunction "1_1") (pintype "passive"))
      (node (ref "L7") (pin "2") (pinfunction "2_2") (pintype "passive"))
      (node (ref "U2") (pin "3") (pinfunction "RXN_3") (pintype "input"))
    )
    (net (code "50") (name "Net-(C6-P$2)") (class "Default")
      (node (ref "C6") (pin "2") (pinfunction "P$2_2") (pintype "passive"))
      (node (ref "L6") (pin "2") (pinfunction "2_2") (pintype "passive"))
      (node (ref "U2") (pin "2") (pinfunction "RXP_2") (pintype "input"))
    )
    (net (code "51") (name "Net-(C11-P$1)") (class "Default")
      (node (ref "C11") (pin "1") (pinfunction "P$1_1") (pintype "passive"))
      (node (ref "C21") (pin "1") (pinfunction "P$1_1") (pintype "passive"))
      (node (ref "C7") (pin "1") (pinfunction "P$1_1") (pintype "passive"))
      (node (ref "C8") (pin "1") (pinfunction "P$1_1") (pintype "passive"))
      (node (ref "FB1") (pin "1") (pinfunction "P$1_1") (pintype "passive"))
      (node (ref "L2") (pin "2") (pinfunction "2_2") (pintype "passive"))
      (node (ref "U2") (pin "6") (pinfunction "VDD_6") (pintype "power_in"))
      (node (ref "U2") (pin "8") (pinfunction "VDD2_8") (pintype "power_in"))
    )
    (net (code "52") (name "Net-(C12-P$1)") (class "Default")
      (node (ref "C12") (pin "1") (pinfunction "P$1_1") (pintype "passive"))
      (node (ref "FB2") (pin "1") (pinfunction "P$1_1") (pintype "passive"))
      (node (ref "U5") (pin "4") (pinfunction "VCC_4") (pintype "power_in"))
    )
    (net (code "53") (name "Net-(C16-P$1)") (class "Default")
      (node (ref "C16") (pin "1") (pinfunction "P$1_1") (pintype "passive"))
      (node (ref "U1") (pin "29") (pinfunction "VDD_CORE_29") (pintype "power_in"))
    )
    (net (code "54") (name "Net-(C20-P$1)") (class "Default")
      (node (ref "C20") (pin "1") (pinfunction "P$1_1") (pintype "passive"))
      (node (ref "U6") (pin "4") (pinfunction "VCC_4") (pintype "power_in"))
      (node (ref "U9") (pin "$19") (pinfunction "VCC_TCXO_$19") (pintype "bidirectional"))
    )
    (net (code "55") (name "Net-(C26-P$2)") (class "Default")
      (node (ref "C26") (pin "2") (pinfunction "P$2_2") (pintype "passive"))
      (node (ref "U$55") (pin "1") (pinfunction "XA_1") (pintype "bidirectional"))
    )
    (net (code "56") (name "Net-(U$55-CLKIN)") (class "Default")
      (node (ref "R14") (pin "1") (pinfunction "1_1") (pintype "passive"))
      (node (ref "U$55") (pin "4") (pinfunction "CLKIN_4") (pintype "bidirectional"))
    )
    (net (code "57") (name "Net-(U$55-INTR)") (class "Default")
      (node (ref "R17") (pin "1") (pinfunction "1_1") (pintype "passive"))
      (node (ref "U$55") (pin "8") (pinfunction "INTR_8") (pintype "bidirectional"))
    )
    (net (code "58") (name "Net-(U$55-XB)") (class "Default")
      (node (ref "R13") (pin "1") (pinfunction "1_1") (pintype "passive"))
      (node (ref "U$55") (pin "2") (pinfunction "XB_2") (pintype "bidirectional"))
    )
    (net (code "59") (name "Net-(U9-CTS_SPI)") (class "Default")
      (node (ref "R4") (pin "1") (pinfunction "1_1") (pintype "passive"))
      (node (ref "U9") (pin "$31") (pinfunction "CTS_SPI_$31") (pintype "bidirectional"))
    )
    (net (code "60") (name "Net-(U9-GPIO0)") (class "Default")
      (node (ref "R6") (pin "2") (pinfunction "2_2") (pintype "passive"))
      (node (ref "U9") (pin "$17") (pinfunction "GPIO0_$17") (pintype "bidirectional"))
    )
    (net (code "61") (name "Net-(U9-GPIO1)") (class "Default")
      (node (ref "R5") (pin "2") (pinfunction "2_2") (pintype "passive"))
      (node (ref "U9") (pin "$16") (pinfunction "GPIO1_$16") (pintype "bidirectional"))
    )
    (net (code "62") (name "Net-(U9-VBB_I)") (class "Default")
      (node (ref "U9") (pin "$6") (pinfunction "VBB_I_$6") (pintype "bidirectional"))
      (node (ref "U9") (pin "$7") (pinfunction "VREG_O_$7") (pintype "bidirectional"))
    )
    (net (code "63") (name "unconnected-(C28-P$2-Pad2)") (class "Default")
      (node (ref "C28") (pin "2") (pinfunction "P$2_2") (pintype "passive"))
    )
    (net (code "64") (name "unconnected-(U$55-CLK0-Pad22)") (class "Default")
      (node (ref "U$55") (pin "22") (pinfunction "CLK0_22") (pintype "bidirectional"))
    )
    (net (code "65") (name "unconnected-(U$55-CLK1-Pad21)") (class "Default")
      (node (ref "U$55") (pin "21") (pinfunction "CLK1_21") (pintype "bidirectional"))
    )
    (net (code "66") (name "unconnected-(U$55-CLK3-Pad17)") (class "Default")
      (node (ref "U$55") (pin "17") (pinfunction "CLK3_17") (pintype "bidirectional"))
    )
    (net (code "67") (name "unconnected-(U$55-CLK4-Pad14)") (class "Default")
      (node (ref "U$55") (pin "14") (pinfunction "CLK4_14") (pintype "bidirectional"))
    )
    (net (code "68") (name "unconnected-(U$55-CLK5-Pad13)") (class "Default")
      (node (ref "U$55") (pin "13") (pinfunction "CLK5_13") (pintype "bidirectional"))
    )
    (net (code "69") (name "unconnected-(U$55-CLK6-Pad10)") (class "Default")
      (node (ref "U$55") (pin "10") (pinfunction "CLK6_10") (pintype "bidirectional"))
    )
    (net (code "70") (name "unconnected-(U$55-CLK7-Pad9)") (class "Default")
      (node (ref "U$55") (pin "9") (pinfunction "CLK7_9") (pintype "bidirectional"))
    )
    (net (code "71") (name "unconnected-(U2-GPIO2-Pad19)") (class "Default")
      (node (ref "U2") (pin "19") (pinfunction "GPIO2_19") (pintype "bidirectional"))
    )
    (net (code "72") (name "unconnected-(U2-GPIO3-Pad20)") (class "Default")
      (node (ref "U2") (pin "20") (pinfunction "GPIO3_20") (pintype "bidirectional"))
    )
    (net (code "73") (name "unconnected-(U2-TXRAMP-Pad7)") (class "Default")
      (node (ref "U2") (pin "7") (pinfunction "TXRAMP_7") (pintype "bidirectional"))
    )
    (net (code "74") (name "unconnected-(U2-XOUT-Pad16)") (class "Default")
      (node (ref "U2") (pin "16") (pinfunction "XOUT_16") (pintype "output"))
    )
    (net (code "75") (name "unconnected-(U3-Pad5_EXTINT0)") (class "Default")
      (node (ref "U3") (pin "5_EXTINT0") (pinfunction "5_EXTINT0_5_EXTINT0") (pintype "bidirectional"))
    )
    (net (code "76") (name "unconnected-(U3-Pad6_V_BCKP)") (class "Default")
      (node (ref "U3") (pin "6_V_BCKP") (pinfunction "6_V_BCKP_6_V_BCKP") (pintype "bidirectional"))
    )
    (net (code "77") (name "unconnected-(U3-Pad13_ANTON)") (class "Default")
      (node (ref "U3") (pin "13_ANTON") (pinfunction "13_ANTON_13_ANTON") (pintype "bidirectional"))
    )
    (net (code "78") (name "unconnected-(U3-Pad14_VCC_RF)") (class "Default")
      (node (ref "U3") (pin "14_VCC_RF") (pinfunction "14_VCC_RF_14_VCC_RF") (pintype "bidirectional"))
    )
    (net (code "79") (name "unconnected-(U3-Pad15_RESERVED)") (class "Default")
      (node (ref "U3") (pin "15_RESERVED") (pinfunction "15_RESERVED_15_RESERVED") (pintype "bidirectional"))
    )
    (net (code "80") (name "unconnected-(U3-Pad16_SDA2)") (class "Default")
      (node (ref "U3") (pin "16_SDA2") (pinfunction "16_SDA2_16_SDA2") (pintype "bidirectional"))
    )
    (net (code "81") (name "unconnected-(U3-Pad17_SCL2)") (class "Default")
      (node (ref "U3") (pin "17_SCL2") (pinfunction "17_SCL2_17_SCL2") (pintype "bidirectional"))
    )
    (net (code "82") (name "unconnected-(U3-Pad18_RESERVED)") (class "Default")
      (node (ref "U3") (pin "18_RESERVED") (pinfunction "18_RESERVED_18_RESERVED") (pintype "bidirectional"))
    )
    (net (code "83") (name "unconnected-(U4-IO3{slash}RESETN-Pad7)") (class "Default")
      (node (ref "U4") (pin "7") (pinfunction "IO3/RESETN_7") (pintype "output"))
    )
    (net (code "84") (name "unconnected-(U5-NC-Pad1)") (class "Default")
      (node (ref "U5") (pin "1") (pinfunction "NC_1") (pintype "no_connect"))
    )
    (net (code "85") (name "unconnected-(U6-NC-Pad1)") (class "Default")
      (node (ref "U6") (pin "1") (pinfunction "NC_1") (pintype "no_connect"))
    )
    (net (code "86") (name "unconnected-(U9-GPIO2-Pad$15)") (class "Default")
      (node (ref "U9") (pin "$15") (pinfunction "GPIO2_$15") (pintype "bidirectional"))
    )
    (net (code "87") (name "unconnected-(U9-GPIO3-Pad$11)") (class "Default")
      (node (ref "U9") (pin "$11") (pinfunction "GPIO3_$11") (pintype "bidirectional"))
    )
    (net (code "88") (name "unconnected-(U9-GPIO4-Pad$14)") (class "Default")
      (node (ref "U9") (pin "$14") (pinfunction "GPIO4_$14") (pintype "bidirectional"))
    )
    (net (code "89") (name "unconnected-(U9-GPIO8-Pad$10)") (class "Default")
      (node (ref "U9") (pin "$10") (pinfunction "GPIO8_$10") (pintype "bidirectional"))
    )
    (net (code "90") (name "unconnected-(U9-RTS_SPI-Pad$32)") (class "Default")
      (node (ref "U9") (pin "$32") (pinfunction "RTS_SPI_$32") (pintype "bidirectional"))
    )
    (net (code "91") (name "unconnected-(U9-SYSTEM_ON-Pad$2)") (class "Default")
      (node (ref "U9") (pin "$2") (pinfunction "SYSTEM_ON_$2") (pintype "bidirectional"))
    )
    (net (code "92") (name "unconnected-(U9-XTAL_CLK-Pad$22)") (class "Default")
      (node (ref "U9") (pin "$22") (pinfunction "XTAL_CLK_$22") (pintype "bidirectional"))
    )
    (net (code "93") (name "unconnected-(U44-NC-Pad2)") (class "Default")
      (node (ref "U44") (pin "2") (pinfunction "NC_2") (pintype "bidirectional"))
    )
  )
)
